# laserboard.net
KiCad netlist of a schematic drawn in EAGLE
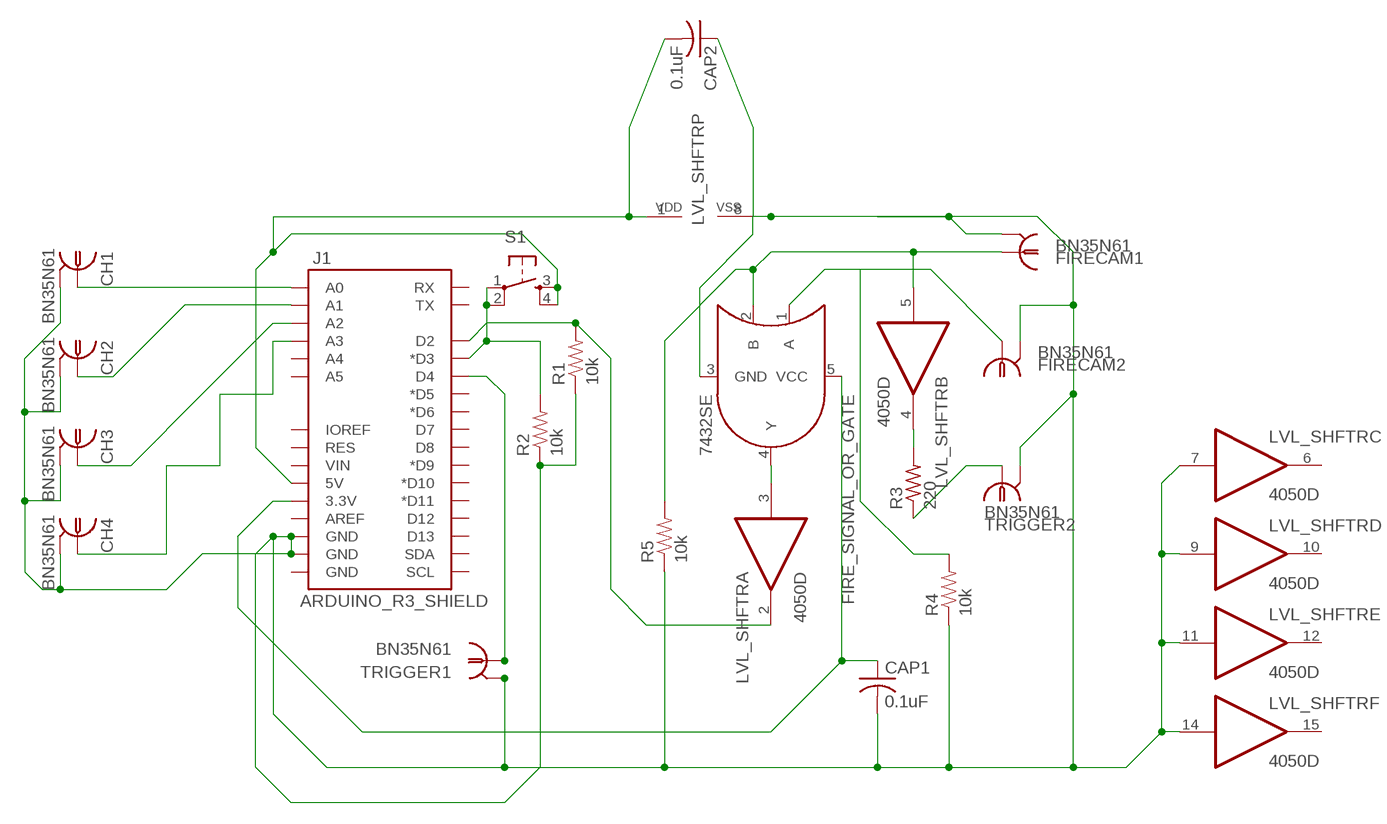
[diagram p0: schematic, sheet 1]

(export (version "E")
  (design (tool "Eeschema 10.0.6"))
  (components
    (comp (ref "CAP1")
      (value "0.1uF")
      (footprint "eagle-import:C1206")
      (libsource (lib "eagle-import") (part "C-USC1206"))
    )
    (comp (ref "CAP2")
      (value "0.1uF")
      (footprint "eagle-import:C1206")
      (libsource (lib "eagle-import") (part "C-USC1206"))
    )
    (comp (ref "CH1")
      (value "BN35N61")
      (footprint "eagle-import:B35N61")
      (libsource (lib "eagle-import") (part "BN35N61"))
    )
    (comp (ref "CH2")
      (value "BN35N61")
      (footprint "eagle-import:B35N61")
      (libsource (lib "eagle-import") (part "BN35N61"))
    )
    (comp (ref "CH3")
      (value "BN35N61")
      (footprint "eagle-import:B35N61")
      (libsource (lib "eagle-import") (part "BN35N61"))
    )
    (comp (ref "CH4")
      (value "BN35N61")
      (footprint "eagle-import:B35N61")
      (libsource (lib "eagle-import") (part "BN35N61"))
    )
    (comp (ref "FIRECAM1")
      (value "BN35N61")
      (footprint "eagle-import:B35N61")
      (libsource (lib "eagle-import") (part "BN35N61"))
    )
    (comp (ref "FIRECAM2")
      (value "BN35N61")
      (footprint "eagle-import:B35N61")
      (libsource (lib "eagle-import") (part "BN35N61"))
    )
    (comp (ref "FIRE_SIGNAL_OR_GATE")
      (value "7432SE")
      (footprint "eagle-import:SOT353")
      (libsource (lib "eagle-import") (part "7432SE"))
    )
    (comp (ref "J1")
      (value "ARDUINO_R3_SHIELD")
      (footprint "eagle-import:UNO_R3_SHIELD")
      (libsource (lib "eagle-import") (part "ARDUINO_R3_SHIELD"))
    )
    (comp (ref "LVL_SHFTR")
      (value "4050D")
      (footprint "eagle-import:SO16")
      (libsource (lib "eagle-import") (part "4050D"))
    )
    (comp (ref "R1")
      (value "10k")
      (footprint "eagle-import:1206")
      (libsource (lib "eagle-import") (part "SparkFun-Resistors_RESISTOR1206"))
    )
    (comp (ref "R2")
      (value "10k")
      (footprint "eagle-import:1206")
      (libsource (lib "eagle-import") (part "RESISTOR1206"))
    )
    (comp (ref "R3")
      (value "220")
      (footprint "eagle-import:M1206")
      (libsource (lib "eagle-import") (part "R-US_M1206"))
    )
    (comp (ref "R4")
      (value "10k")
      (footprint "eagle-import:1206")
      (libsource (lib "eagle-import") (part "SparkFun-Resistors_RESISTOR1206"))
    )
    (comp (ref "R5")
      (value "10k")
      (footprint "eagle-import:1206")
      (libsource (lib "eagle-import") (part "SparkFun-Resistors_RESISTOR1206"))
    )
    (comp (ref "S1")
      (value "TAC_SWITCHPTH")
      (footprint "eagle-import:TACTILE-PTH")
      (libsource (lib "eagle-import") (part "TAC_SWITCHPTH"))
    )
    (comp (ref "TRIGGER1")
      (value "BN35N61")
      (footprint "eagle-import:B35N61")
      (libsource (lib "eagle-import") (part "BN35N61"))
    )
    (comp (ref "TRIGGER2")
      (value "BN35N61")
      (footprint "eagle-import:B35N61")
      (libsource (lib "eagle-import") (part "BN35N61"))
    )
  )
  (nets
    (net (code "1") (name "Net-(CH1-Pad1)") (class "Default")
      (node (ref "CH1") (pin "1") (pinfunction "1_1") (pintype "passive"))
      (node (ref "J1") (pin "A0") (pinfunction "A0_A0") (pintype "bidirectional"))
    )
    (net (code "2") (name "Net-(CH2-Pad1)") (class "Default")
      (node (ref "CH2") (pin "1") (pinfunction "1_1") (pintype "passive"))
      (node (ref "J1") (pin "A1") (pinfunction "A1_A1") (pintype "bidirectional"))
    )
    (net (code "3") (name "Net-(CH3-Pad1)") (class "Default")
      (node (ref "CH3") (pin "1") (pinfunction "1_1") (pintype "passive"))
      (node (ref "J1") (pin "A2") (pinfunction "A2_A2") (pintype "bidirectional"))
    )
    (net (code "4") (name "Net-(CH4-Pad1)") (class "Default")
      (node (ref "CH4") (pin "1") (pinfunction "1_1") (pintype "passive"))
      (node (ref "J1") (pin "A3") (pinfunction "A3_A3") (pintype "bidirectional"))
    )
    (net (code "5") (name "Net-(FIRE_SIGNAL_OR_GATE-A)") (class "Default")
      (node (ref "FIRECAM2") (pin "1") (pinfunction "1_1") (pintype "passive"))
      (node (ref "FIRE_SIGNAL_OR_GATE") (pin "1") (pinfunction "A_1") (pintype "bidirectional"))
      (node (ref "R4") (pin "2") (pinfunction "2_2") (pintype "passive"))
    )
    (net (code "6") (name "Net-(FIRE_SIGNAL_OR_GATE-B)") (class "Default")
      (node (ref "FIRECAM1") (pin "1") (pinfunction "1_1") (pintype "passive"))
      (node (ref "FIRE_SIGNAL_OR_GATE") (pin "2") (pinfunction "B_2") (pintype "bidirectional"))
      (node (ref "LVL_SHFTR") (pin "5") (pinfunction "I_5") (pintype "input"))
      (node (ref "R5") (pin "2") (pinfunction "2_2") (pintype "passive"))
    )
    (net (code "7") (name "Net-(FIRE_SIGNAL_OR_GATE-GND)") (class "Default")
      (node (ref "CAP1") (pin "2") (pinfunction "2_2") (pintype "passive"))
      (node (ref "CAP2") (pin "1") (pinfunction "1_1") (pintype "passive"))
      (node (ref "CH1") (pin "2") (pinfunction "2_2") (pintype "passive"))
      (node (ref "CH1") (pin "3") (pinfunction "2_3") (pintype "passive"))
      (node (ref "CH1") (pin "4") (pinfunction "2_4") (pintype "passive"))
      (node (ref "CH1") (pin "5") (pinfunction "2_5") (pintype "passive"))
      (node (ref "CH2") (pin "2") (pinfunction "2_2") (pintype "passive"))
      (node (ref "CH2") (pin "3") (pinfunction "2_3") (pintype "passive"))
      (node (ref "CH2") (pin "4") (pinfunction "2_4") (pintype "passive"))
      (node (ref "CH2") (pin "5") (pinfunction "2_5") (pintype "passive"))
      (node (ref "CH3") (pin "2") (pinfunction "2_2") (pintype "passive"))
      (node (ref "CH3") (pin "3") (pinfunction "2_3") (pintype "passive"))
      (node (ref "CH3") (pin "4") (pinfunction "2_4") (pintype "passive"))
      (node (ref "CH3") (pin "5") (pinfunction "2_5") (pintype "passive"))
      (node (ref "CH4") (pin "2") (pinfunction "2_2") (pintype "passive"))
      (node (ref "CH4") (pin "3") (pinfunction "2_3") (pintype "passive"))
      (node (ref "CH4") (pin "4") (pinfunction "2_4") (pintype "passive"))
      (node (ref "CH4") (pin "5") (pinfunction "2_5") (pintype "passive"))
      (node (ref "FIRECAM1") (pin "2") (pinfunction "2_2") (pintype "passive"))
      (node (ref "FIRECAM1") (pin "3") (pinfunction "2_3") (pintype "passive"))
      (node (ref "FIRECAM1") (pin "4") (pinfunction "2_4") (pintype "passive"))
      (node (ref "FIRECAM1") (pin "5") (pinfunction "2_5") (pintype "passive"))
      (node (ref "FIRECAM2") (pin "2") (pinfunction "2_2") (pintype "passive"))
      (node (ref "FIRECAM2") (pin "3") (pinfunction "2_3") (pintype "passive"))
      (node (ref "FIRECAM2") (pin "4") (pinfunction "2_4") (pintype "passive"))
      (node (ref "FIRECAM2") (pin "5") (pinfunction "2_5") (pintype "passive"))
      (node (ref "FIRE_SIGNAL_OR_GATE") (pin "3") (pinfunction "GND_3") (pintype "bidirectional"))
      (node (ref "J1") (pin "GND@1") (pinfunction "GND_GND@1") (pintype "bidirectional"))
      (node (ref "J1") (pin "GND@2") (pinfunction "GND_GND@2") (pintype "bidirectional"))
      (node (ref "LVL_SHFTR") (pin "11") (pinfunction "I_11") (pintype "input"))
      (node (ref "LVL_SHFTR") (pin "14") (pinfunction "I_14") (pintype "input"))
      (node (ref "LVL_SHFTR") (pin "7") (pinfunction "I_7") (pintype "input"))
      (node (ref "LVL_SHFTR") (pin "8") (pinfunction "VSS_8") (pintype "power_in"))
      (node (ref "LVL_SHFTR") (pin "9") (pinfunction "I_9") (pintype "input"))
      (node (ref "R1") (pin "1") (pinfunction "1_1") (pintype "passive"))
      (node (ref "R2") (pin "1") (pinfunction "1_1") (pintype "passive"))
      (node (ref "R4") (pin "1") (pinfunction "1_1") (pintype "passive"))
      (node (ref "R5") (pin "1") (pinfunction "1_1") (pintype "passive"))
      (node (ref "TRIGGER1") (pin "2") (pinfunction "2_2") (pintype "passive"))
      (node (ref "TRIGGER1") (pin "3") (pinfunction "2_3") (pintype "passive"))
      (node (ref "TRIGGER1") (pin "4") (pinfunction "2_4") (pintype "passive"))
      (node (ref "TRIGGER1") (pin "5") (pinfunction "2_5") (pintype "passive"))
      (node (ref "TRIGGER2") (pin "2") (pinfunction "2_2") (pintype "passive"))
      (node (ref "TRIGGER2") (pin "3") (pinfunction "2_3") (pintype "passive"))
      (node (ref "TRIGGER2") (pin "4") (pinfunction "2_4") (pintype "passive"))
      (node (ref "TRIGGER2") (pin "5") (pinfunction "2_5") (pintype "passive"))
    )
    (net (code "8") (name "Net-(FIRE_SIGNAL_OR_GATE-VCC)") (class "Default")
      (node (ref "CAP1") (pin "1") (pinfunction "1_1") (pintype "passive"))
      (node (ref "FIRE_SIGNAL_OR_GATE") (pin "5") (pinfunction "VCC_5") (pintype "bidirectional"))
      (node (ref "J1") (pin "3.3V") (pinfunction "3.3V_3.3V") (pintype "bidirectional"))
    )
    (net (code "9") (name "Net-(FIRE_SIGNAL_OR_GATE-Y)") (class "Default")
      (node (ref "FIRE_SIGNAL_OR_GATE") (pin "4") (pinfunction "Y_4") (pintype "bidirectional"))
      (node (ref "LVL_SHFTR") (pin "3") (pinfunction "I_3") (pintype "input"))
    )
    (net (code "10") (name "Net-(J1-*D3)") (class "Default")
      (node (ref "J1") (pin "D3") (pinfunction "*D3_D3") (pintype "bidirectional"))
      (node (ref "R2") (pin "2") (pinfunction "2_2") (pintype "passive"))
      (node (ref "S1") (pin "1") (pinfunction "1_1") (pintype "passive"))
      (node (ref "S1") (pin "2") (pinfunction "2_2") (pintype "passive"))
    )
    (net (code "11") (name "Net-(J1-PadD4)") (class "Default")
      (node (ref "J1") (pin "D4") (pinfunction "D4_D4") (pintype "bidirectional"))
      (node (ref "TRIGGER1") (pin "1") (pinfunction "1_1") (pintype "passive"))
    )
    (net (code "12") (name "Net-(LVL_SHFTRA-O)") (class "Default")
      (node (ref "J1") (pin "D2") (pinfunction "D2_D2") (pintype "bidirectional"))
      (node (ref "LVL_SHFTR") (pin "2") (pinfunction "O_2") (pintype "output"))
      (node (ref "R1") (pin "2") (pinfunction "2_2") (pintype "passive"))
    )
    (net (code "13") (name "Net-(LVL_SHFTRB-O)") (class "Default")
      (node (ref "LVL_SHFTR") (pin "4") (pinfunction "O_4") (pintype "output"))
      (node (ref "R3") (pin "2") (pinfunction "2_2") (pintype "passive"))
    )
    (net (code "14") (name "Net-(LVL_SHFTRG-VDD)") (class "Default")
      (node (ref "CAP2") (pin "2") (pinfunction "2_2") (pintype "passive"))
      (node (ref "J1") (pin "5V") (pinfunction "5V_5V") (pintype "bidirectional"))
      (node (ref "LVL_SHFTR") (pin "1") (pinfunction "VDD_1") (pintype "power_in"))
      (node (ref "S1") (pin "3") (pinfunction "3_3") (pintype "passive"))
      (node (ref "S1") (pin "4") (pinfunction "4_4") (pintype "passive"))
    )
    (net (code "15") (name "Net-(R3-Pad1)") (class "Default")
      (node (ref "R3") (pin "1") (pinfunction "1_1") (pintype "passive"))
      (node (ref "TRIGGER2") (pin "1") (pinfunction "1_1") (pintype "passive"))
    )
    (net (code "16") (name "unconnected-(J1-*D5-PadD5)") (class "Default")
      (node (ref "J1") (pin "D5") (pinfunction "*D5_D5") (pintype "bidirectional"))
    )
    (net (code "17") (name "unconnected-(J1-*D6-PadD6)") (class "Default")
      (node (ref "J1") (pin "D6") (pinfunction "*D6_D6") (pintype "bidirectional"))
    )
    (net (code "18") (name "unconnected-(J1-*D9-PadD9)") (class "Default")
      (node (ref "J1") (pin "D9") (pinfunction "*D9_D9") (pintype "bidirectional"))
    )
    (net (code "19") (name "unconnected-(J1-*D10-PadD10)") (class "Default")
      (node (ref "J1") (pin "D10") (pinfunction "*D10_D10") (pintype "bidirectional"))
    )
    (net (code "20") (name "unconnected-(J1-*D11-PadD11)") (class "Default")
      (node (ref "J1") (pin "D11") (pinfunction "*D11_D11") (pintype "bidirectional"))
    )
    (net (code "21") (name "unconnected-(J1-GND-PadGND@0)") (class "Default")
      (node (ref "J1") (pin "GND@0") (pinfunction "GND_GND@0") (pintype "bidirectional"))
    )
    (net (code "22") (name "unconnected-(J1-PadA4)") (class "Default")
      (node (ref "J1") (pin "A4") (pinfunction "A4_A4") (pintype "bidirectional"))
    )
    (net (code "23") (name "unconnected-(J1-PadA5)") (class "Default")
      (node (ref "J1") (pin "A5") (pinfunction "A5_A5") (pintype "bidirectional"))
    )
    (net (code "24") (name "unconnected-(J1-PadAREF)") (class "Default")
      (node (ref "J1") (pin "AREF") (pinfunction "AREF_AREF") (pintype "bidirectional"))
    )
    (net (code "25") (name "unconnected-(J1-PadD7)") (class "Default")
      (node (ref "J1") (pin "D7") (pinfunction "D7_D7") (pintype "bidirectional"))
    )
    (net (code "26") (name "unconnected-(J1-PadD8)") (class "Default")
      (node (ref "J1") (pin "D8") (pinfunction "D8_D8") (pintype "bidirectional"))
    )
    (net (code "27") (name "unconnected-(J1-PadD12)") (class "Default")
      (node (ref "J1") (pin "D12") (pinfunction "D12_D12") (pintype "bidirectional"))
    )
    (net (code "28") (name "unconnected-(J1-PadD13)") (class "Default")
      (node (ref "J1") (pin "D13") (pinfunction "D13_D13") (pintype "bidirectional"))
    )
    (net (code "29") (name "unconnected-(J1-PadIOREF)") (class "Default")
      (node (ref "J1") (pin "IOREF") (pinfunction "IOREF_IOREF") (pintype "bidirectional"))
    )
    (net (code "30") (name "unconnected-(J1-PadRES)") (class "Default")
      (node (ref "J1") (pin "RES") (pinfunction "RES_RES") (pintype "bidirectional"))
    )
    (net (code "31") (name "unconnected-(J1-PadRX)") (class "Default")
      (node (ref "J1") (pin "RX") (pinfunction "RX_RX") (pintype "bidirectional"))
    )
    (net (code "32") (name "unconnected-(J1-PadSCL)") (class "Default")
      (node (ref "J1") (pin "SCL") (pinfunction "SCL_SCL") (pintype "bidirectional"))
    )
    (net (code "33") (name "unconnected-(J1-PadSDA)") (class "Default")
      (node (ref "J1") (pin "SDA") (pinfunction "SDA_SDA") (pintype "bidirectional"))
    )
    (net (code "34") (name "unconnected-(J1-PadTX)") (class "Default")
      (node (ref "J1") (pin "TX") (pinfunction "TX_TX") (pintype "bidirectional"))
    )
    (net (code "35") (name "unconnected-(J1-PadVIN)") (class "Default")
      (node (ref "J1") (pin "VIN") (pinfunction "VIN_VIN") (pintype "bidirectional"))
    )
    (net (code "36") (name "unconnected-(LVL_SHFTRC-O-Pad6)") (class "Default")
      (node (ref "LVL_SHFTR") (pin "6") (pinfunction "O_6") (pintype "output"))
    )
    (net (code "37") (name "unconnected-(LVL_SHFTRD-O-Pad10)") (class "Default")
      (node (ref "LVL_SHFTR") (pin "10") (pinfunction "O_10") (pintype "output"))
    )
    (net (code "38") (name "unconnected-(LVL_SHFTRE-O-Pad12)") (class "Default")
      (node (ref "LVL_SHFTR") (pin "12") (pinfunction "O_12") (pintype "output"))
    )
    (net (code "39") (name "unconnected-(LVL_SHFTRF-O-Pad15)") (class "Default")
      (node (ref "LVL_SHFTR") (pin "15") (pinfunction "O_15") (pintype "output"))
    )
  )
)
